# ext_power.net
KiCad netlist of a schematic drawn in Altium Designer
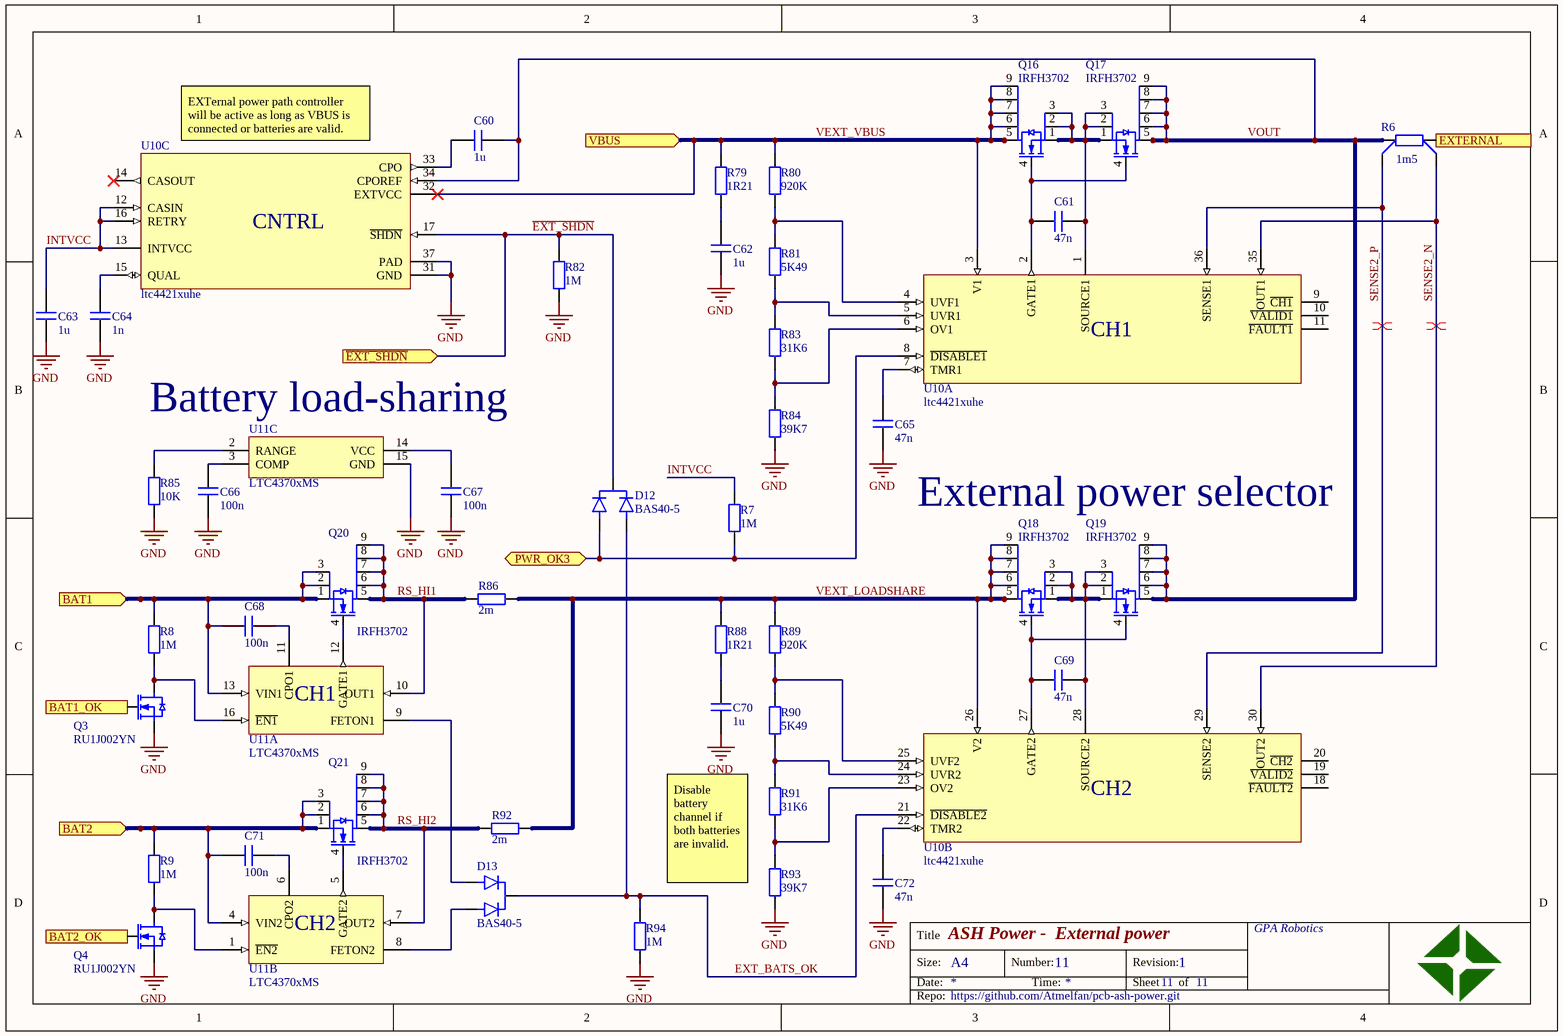
[diagram p0: ext_power.SchDoc]

(export (version "E")
  (design (tool "Eeschema 10.0.6"))
  (components
    (comp (ref "C60")
      (value "1u")
      (footprint "CAPC2012X11N")
      (description "Capacitor")
      (fields (field (name "Comment") "cap"))
      (libsource (lib "lib_passives") (part "cap"))
    )
    (comp (ref "C61")
      (value "47n")
      (footprint "CAPC1005X06N")
      (description "Capacitor")
      (fields (field (name "Comment") "cap"))
      (libsource (lib "lib_passives") (part "cap"))
    )
    (comp (ref "C62")
      (value "1u")
      (footprint "CAPC2012X11N")
      (description "Capacitor")
      (fields (field (name "Comment") "cap"))
      (libsource (lib "lib_passives") (part "cap"))
    )
    (comp (ref "C63")
      (value "1u")
      (footprint "CAPC2012X11N")
      (description "Capacitor")
      (fields (field (name "Comment") "cap"))
      (libsource (lib "lib_passives") (part "cap"))
    )
    (comp (ref "C64")
      (value "1n")
      (footprint "CAPC1005X06N")
      (description "Capacitor")
      (fields (field (name "Comment") "cap"))
      (libsource (lib "lib_passives") (part "cap"))
    )
    (comp (ref "C65")
      (value "47n")
      (footprint "CAPC1005X06N")
      (description "Capacitor")
      (fields (field (name "Comment") "cap"))
      (libsource (lib "lib_passives") (part "cap"))
    )
    (comp (ref "C66")
      (value "100n")
      (footprint "CAPC1005X06N")
      (description "Capacitor")
      (fields (field (name "Comment") "cap"))
      (libsource (lib "lib_passives") (part "cap"))
    )
    (comp (ref "C67")
      (value "100n")
      (footprint "CAPC1005X06N")
      (description "Capacitor")
      (fields (field (name "Comment") "cap"))
      (libsource (lib "lib_passives") (part "cap"))
    )
    (comp (ref "C68")
      (value "100n")
      (footprint "CAPC1005X06N")
      (description "Capacitor")
      (fields (field (name "Comment") "cap"))
      (libsource (lib "lib_passives") (part "cap"))
    )
    (comp (ref "C69")
      (value "47n")
      (footprint "CAPC1005X06N")
      (description "Capacitor")
      (fields (field (name "Comment") "cap"))
      (libsource (lib "lib_passives") (part "cap"))
    )
    (comp (ref "C70")
      (value "1u")
      (footprint "CAPC2012X11N")
      (description "Capacitor")
      (fields (field (name "Comment") "cap"))
      (libsource (lib "lib_passives") (part "cap"))
    )
    (comp (ref "C71")
      (value "100n")
      (footprint "CAPC1005X06N")
      (description "Capacitor")
      (fields (field (name "Comment") "cap"))
      (libsource (lib "lib_passives") (part "cap"))
    )
    (comp (ref "C72")
      (value "47n")
      (footprint "CAPC1005X06N")
      (description "Capacitor")
      (fields (field (name "Comment") "cap"))
      (libsource (lib "lib_passives") (part "cap"))
    )
    (comp (ref "D12")
      (value "BAS40-5")
      (footprint "SOT23_CC")
      (description "Diode Common Cathode")
      (libsource (lib "lib_actives") (part "diode_dual_cc"))
    )
    (comp (ref "D13")
      (value "BAS40-5")
      (footprint "SOT23_CC")
      (description "Diode Common Cathode")
      (libsource (lib "lib_actives") (part "diode_dual_cc"))
    )
    (comp (ref "Q3")
      (value "RU1J002YN")
      (footprint "SOTFL65P210X105-3N")
      (description "N-channel 50V 200mA Small signal MOSFET")
      (libsource (lib "lib_rohm") (part "ru1j002yn"))
    )
    (comp (ref "Q4")
      (value "RU1J002YN")
      (footprint "SOTFL65P210X105-3N")
      (description "N-channel 50V 200mA Small signal MOSFET")
      (libsource (lib "lib_rohm") (part "ru1j002yn"))
    )
    (comp (ref "Q16")
      (value "IRFH3702")
      (footprint "PQFN67P300X300X100-8N")
      (description "HEXFET Power MOSFET")
      (libsource (lib "lib_infineon") (part "irfh3702"))
    )
    (comp (ref "Q17")
      (value "IRFH3702")
      (footprint "PQFN67P300X300X100-8N")
      (description "HEXFET Power MOSFET")
      (libsource (lib "lib_infineon") (part "irfh3702"))
    )
    (comp (ref "Q18")
      (value "IRFH3702")
      (footprint "PQFN67P300X300X100-8N")
      (description "HEXFET Power MOSFET")
      (libsource (lib "lib_infineon") (part "irfh3702"))
    )
    (comp (ref "Q19")
      (value "IRFH3702")
      (footprint "PQFN67P300X300X100-8N")
      (description "HEXFET Power MOSFET")
      (libsource (lib "lib_infineon") (part "irfh3702"))
    )
    (comp (ref "Q20")
      (value "IRFH3702")
      (footprint "PQFN67P300X300X100-8N")
      (description "HEXFET Power MOSFET")
      (libsource (lib "lib_infineon") (part "irfh3702"))
    )
    (comp (ref "Q21")
      (value "IRFH3702")
      (footprint "PQFN67P300X300X100-8N")
      (description "HEXFET Power MOSFET")
      (libsource (lib "lib_infineon") (part "irfh3702"))
    )
    (comp (ref "R6")
      (value "1m5")
      (footprint "4T_RESC1632X05N")
      (description "Resistor")
      (fields (field (name "Comment") "res_4t"))
      (libsource (lib "lib_passives") (part "res_4t"))
    )
    (comp (ref "R7")
      (value "1M")
      (footprint "RESC1005X04N")
      (description "Resistor")
      (fields (field (name "Comment") "res"))
      (libsource (lib "") (part "res_1"))
    )
    (comp (ref "R8")
      (value "1M")
      (footprint "RESC1005X04N")
      (description "Resistor")
      (fields (field (name "Comment") "res"))
      (libsource (lib "lib_passives") (part "res"))
    )
    (comp (ref "R9")
      (value "1M")
      (footprint "RESC1005X04N")
      (description "Resistor")
      (fields (field (name "Comment") "res"))
      (libsource (lib "lib_passives") (part "res"))
    )
    (comp (ref "R79")
      (value "1R21")
      (footprint "RESC2012X06N")
      (description "Resistor")
      (fields (field (name "Comment") "res"))
      (libsource (lib "lib_passives") (part "res"))
    )
    (comp (ref "R80")
      (value "920K")
      (footprint "RESC1005X04N")
      (description "Resistor")
      (fields (field (name "Comment") "res"))
      (libsource (lib "lib_passives") (part "res"))
    )
    (comp (ref "R81")
      (value "5K49")
      (footprint "RESC1005X04N")
      (description "Resistor")
      (fields (field (name "Comment") "res"))
      (libsource (lib "lib_passives") (part "res"))
    )
    (comp (ref "R82")
      (value "1M")
      (footprint "RESC1005X04N")
      (description "Resistor")
      (fields (field (name "Comment") "res"))
      (libsource (lib "") (part "res_1"))
    )
    (comp (ref "R83")
      (value "31K6")
      (footprint "RESC1005X04N")
      (description "Resistor")
      (fields (field (name "Comment") "res"))
      (libsource (lib "lib_passives") (part "res"))
    )
    (comp (ref "R84")
      (value "39K7")
      (footprint "RESC1005X04N")
      (description "Resistor")
      (fields (field (name "Comment") "res"))
      (libsource (lib "lib_passives") (part "res"))
    )
    (comp (ref "R85")
      (value "10K")
      (footprint "RESC1005X04N")
      (description "Resistor")
      (fields (field (name "Comment") "res"))
      (libsource (lib "lib_passives") (part "res"))
    )
    (comp (ref "R86")
      (value "2m")
      (footprint "RESC3216X07N")
      (description "Resistor")
      (fields (field (name "Comment") "res"))
      (libsource (lib "") (part "res_1"))
    )
    (comp (ref "R88")
      (value "1R21")
      (footprint "RESC2012X06N")
      (description "Resistor")
      (fields (field (name "Comment") "res"))
      (libsource (lib "lib_passives") (part "res"))
    )
    (comp (ref "R89")
      (value "920K")
      (footprint "RESC1005X04N")
      (description "Resistor")
      (fields (field (name "Comment") "res"))
      (libsource (lib "lib_passives") (part "res"))
    )
    (comp (ref "R90")
      (value "5K49")
      (footprint "RESC1005X04N")
      (description "Resistor")
      (fields (field (name "Comment") "res"))
      (libsource (lib "lib_passives") (part "res"))
    )
    (comp (ref "R91")
      (value "31K6")
      (footprint "RESC1005X04N")
      (description "Resistor")
      (fields (field (name "Comment") "res"))
      (libsource (lib "lib_passives") (part "res"))
    )
    (comp (ref "R92")
      (value "2m")
      (footprint "RESC3216X07N")
      (description "Resistor")
      (fields (field (name "Comment") "res"))
      (libsource (lib "") (part "res_1"))
    )
    (comp (ref "R93")
      (value "39K7")
      (footprint "RESC1005X04N")
      (description "Resistor")
      (fields (field (name "Comment") "res"))
      (libsource (lib "lib_passives") (part "res"))
    )
    (comp (ref "R94")
      (value "1M")
      (footprint "RESC1005X04N")
      (description "Resistor")
      (fields (field (name "Comment") "res"))
      (libsource (lib "lib_passives") (part "res"))
    )
    (comp (ref "U10")
      (value "ltc4421xuhe")
      (footprint "QFN50P500X600X80_HS-37N_LTC4421")
      (description "High Power Prioritized PowerPath Controller")
      (libsource (lib "lib_analog") (part "ltc4421xuhe"))
    )
    (comp (ref "U11")
      (value "LTC4370xMS")
      (footprint "TSSOP50P510X110-16N_ltc4421")
      (description "Two-Supply Diode-OR Current Balancing Controller")
      (libsource (lib "lib_analog") (part "ltc4370xms"))
    )
  )
  (nets
    (net (code "1") (name "/BAT1") (class "Default")
      (node (ref "C68") (pin "1") (pinfunction "1_1") (pintype "passive"))
      (node (ref "Q20") (pin "1") (pinfunction "S_1") (pintype "passive"))
      (node (ref "Q20") (pin "2") (pinfunction "S_2") (pintype "passive"))
      (node (ref "Q20") (pin "3") (pinfunction "S_3") (pintype "passive"))
      (node (ref "R8") (pin "2") (pinfunction "2_2") (pintype "passive"))
      (node (ref "U11") (pin "13") (pinfunction "VIN1_13") (pintype "input"))
    )
    (net (code "2") (name "/BAT1_OK") (class "Default")
      (node (ref "Q3") (pin "1") (pinfunction "G_1") (pintype "passive"))
    )
    (net (code "3") (name "/BAT2") (class "Default")
      (node (ref "C71") (pin "1") (pinfunction "1_1") (pintype "passive"))
      (node (ref "Q21") (pin "1") (pinfunction "S_1") (pintype "passive"))
      (node (ref "Q21") (pin "2") (pinfunction "S_2") (pintype "passive"))
      (node (ref "Q21") (pin "3") (pinfunction "S_3") (pintype "passive"))
      (node (ref "R9") (pin "2") (pinfunction "2_2") (pintype "passive"))
      (node (ref "U11") (pin "4") (pinfunction "VIN2_4") (pintype "input"))
    )
    (net (code "4") (name "/BAT2_OK") (class "Default")
      (node (ref "Q4") (pin "1") (pinfunction "G_1") (pintype "passive"))
    )
    (net (code "5") (name "/EXTERNAL") (class "Default")
      (node (ref "R6") (pin "2") (pinfunction "2_2") (pintype "passive"))
    )
    (net (code "6") (name "/EXT_BATS_OK") (class "Default")
      (node (ref "D12") (pin "A1") (pinfunction "A1_A1") (pintype "passive"))
      (node (ref "D13") (pin "C") (pinfunction "C_C") (pintype "passive"))
      (node (ref "R94") (pin "2") (pinfunction "2_2") (pintype "passive"))
      (node (ref "U10") (pin "21") (pinfunction "DISABLE2_21") (pintype "input"))
    )
    (net (code "7") (name "/EXT_SHDN") (class "Default")
      (node (ref "D12") (pin "C") (pinfunction "C_C") (pintype "passive"))
      (node (ref "R82") (pin "2") (pinfunction "2_2") (pintype "passive"))
      (node (ref "U10") (pin "17") (pinfunction "SHDN_17") (pintype "input"))
    )
    (net (code "8") (name "/INTVCC") (class "Default")
      (node (ref "C63") (pin "2") (pinfunction "2_2") (pintype "passive"))
      (node (ref "R7") (pin "2") (pinfunction "2_2") (pintype "passive"))
      (node (ref "U10") (pin "12") (pinfunction "CASIN_12") (pintype "input"))
      (node (ref "U10") (pin "13") (pinfunction "INTVCC_13") (pintype "power_in"))
      (node (ref "U10") (pin "16") (pinfunction "RETRY_16") (pintype "input"))
    )
    (net (code "9") (name "/PWR_OK3") (class "Default")
      (node (ref "D12") (pin "A2") (pinfunction "A2_A2") (pintype "passive"))
      (node (ref "R7") (pin "1") (pinfunction "1_1") (pintype "passive"))
      (node (ref "U10") (pin "8") (pinfunction "DISABLE1_8") (pintype "input"))
    )
    (net (code "10") (name "/RS_HI1") (class "Default")
      (node (ref "Q20") (pin "5") (pinfunction "D_5") (pintype "passive"))
      (node (ref "Q20") (pin "6") (pinfunction "D_6") (pintype "passive"))
      (node (ref "Q20") (pin "7") (pinfunction "D_7") (pintype "passive"))
      (node (ref "Q20") (pin "8") (pinfunction "D_8") (pintype "passive"))
      (node (ref "Q20") (pin "9") (pinfunction "D_9") (pintype "passive"))
      (node (ref "R86") (pin "1") (pinfunction "1_1") (pintype "passive"))
      (node (ref "U11") (pin "10") (pinfunction "OUT1_10") (pintype "input"))
    )
    (net (code "11") (name "/RS_HI2") (class "Default")
      (node (ref "Q21") (pin "5") (pinfunction "D_5") (pintype "passive"))
      (node (ref "Q21") (pin "6") (pinfunction "D_6") (pintype "passive"))
      (node (ref "Q21") (pin "7") (pinfunction "D_7") (pintype "passive"))
      (node (ref "Q21") (pin "8") (pinfunction "D_8") (pintype "passive"))
      (node (ref "Q21") (pin "9") (pinfunction "D_9") (pintype "passive"))
      (node (ref "R92") (pin "1") (pinfunction "1_1") (pintype "passive"))
      (node (ref "U11") (pin "7") (pinfunction "OUT2_7") (pintype "input"))
    )
    (net (code "12") (name "/SENSE2_N") (class "Default")
      (node (ref "R6") (pin "4") (pinfunction "4_4") (pintype "passive"))
      (node (ref "U10") (pin "30") (pinfunction "OUT2_30") (pintype "input"))
      (node (ref "U10") (pin "35") (pinfunction "OUT1_35") (pintype "input"))
    )
    (net (code "13") (name "/SENSE2_P") (class "Default")
      (node (ref "R6") (pin "3") (pinfunction "3_3") (pintype "passive"))
      (node (ref "U10") (pin "29") (pinfunction "SENSE2_29") (pintype "input"))
      (node (ref "U10") (pin "36") (pinfunction "SENSE1_36") (pintype "input"))
    )
    (net (code "14") (name "/VEXT_LOADSHARE") (class "Default")
      (node (ref "Q18") (pin "5") (pinfunction "D_5") (pintype "passive"))
      (node (ref "Q18") (pin "6") (pinfunction "D_6") (pintype "passive"))
      (node (ref "Q18") (pin "7") (pinfunction "D_7") (pintype "passive"))
      (node (ref "Q18") (pin "8") (pinfunction "D_8") (pintype "passive"))
      (node (ref "Q18") (pin "9") (pinfunction "D_9") (pintype "passive"))
      (node (ref "R86") (pin "2") (pinfunction "2_2") (pintype "passive"))
      (node (ref "R88") (pin "2") (pinfunction "2_2") (pintype "passive"))
      (node (ref "R89") (pin "2") (pinfunction "2_2") (pintype "passive"))
      (node (ref "R92") (pin "2") (pinfunction "2_2") (pintype "passive"))
      (node (ref "U10") (pin "26") (pinfunction "V2_26") (pintype "input"))
    )
    (net (code "15") (name "/VEXT_VBUS") (class "Default")
      (node (ref "Q16") (pin "5") (pinfunction "D_5") (pintype "passive"))
      (node (ref "Q16") (pin "6") (pinfunction "D_6") (pintype "passive"))
      (node (ref "Q16") (pin "7") (pinfunction "D_7") (pintype "passive"))
      (node (ref "Q16") (pin "8") (pinfunction "D_8") (pintype "passive"))
      (node (ref "Q16") (pin "9") (pinfunction "D_9") (pintype "passive"))
      (node (ref "R79") (pin "2") (pinfunction "2_2") (pintype "passive"))
      (node (ref "R80") (pin "2") (pinfunction "2_2") (pintype "passive"))
      (node (ref "U10") (pin "3") (pinfunction "V1_3") (pintype "input"))
      (node (ref "U10") (pin "32") (pinfunction "EXTVCC_32") (pintype "power_in"))
    )
    (net (code "16") (name "/VOUT") (class "Default")
      (node (ref "C60") (pin "2") (pinfunction "2_2") (pintype "passive"))
      (node (ref "Q17") (pin "5") (pinfunction "D_5") (pintype "passive"))
      (node (ref "Q17") (pin "6") (pinfunction "D_6") (pintype "passive"))
      (node (ref "Q17") (pin "7") (pinfunction "D_7") (pintype "passive"))
      (node (ref "Q17") (pin "8") (pinfunction "D_8") (pintype "passive"))
      (node (ref "Q17") (pin "9") (pinfunction "D_9") (pintype "passive"))
      (node (ref "Q19") (pin "5") (pinfunction "D_5") (pintype "passive"))
      (node (ref "Q19") (pin "6") (pinfunction "D_6") (pintype "passive"))
      (node (ref "Q19") (pin "7") (pinfunction "D_7") (pintype "passive"))
      (node (ref "Q19") (pin "8") (pinfunction "D_8") (pintype "passive"))
      (node (ref "Q19") (pin "9") (pinfunction "D_9") (pintype "passive"))
      (node (ref "R6") (pin "1") (pinfunction "1_1") (pintype "passive"))
      (node (ref "U10") (pin "34") (pinfunction "CPOREF_34") (pintype "input"))
    )
    (net (code "17") (name "GND") (class "Default")
      (node (ref "C62") (pin "1") (pinfunction "1_1") (pintype "passive"))
      (node (ref "C63") (pin "1") (pinfunction "1_1") (pintype "passive"))
      (node (ref "C64") (pin "1") (pinfunction "1_1") (pintype "passive"))
      (node (ref "C65") (pin "1") (pinfunction "1_1") (pintype "passive"))
      (node (ref "C66") (pin "1") (pinfunction "1_1") (pintype "passive"))
      (node (ref "C67") (pin "1") (pinfunction "1_1") (pintype "passive"))
      (node (ref "C70") (pin "1") (pinfunction "1_1") (pintype "passive"))
      (node (ref "C72") (pin "1") (pinfunction "1_1") (pintype "passive"))
      (node (ref "Q3") (pin "2") (pinfunction "S_2") (pintype "passive"))
      (node (ref "Q4") (pin "2") (pinfunction "S_2") (pintype "passive"))
      (node (ref "R82") (pin "1") (pinfunction "1_1") (pintype "passive"))
      (node (ref "R84") (pin "1") (pinfunction "1_1") (pintype "passive"))
      (node (ref "R85") (pin "1") (pinfunction "1_1") (pintype "passive"))
      (node (ref "R93") (pin "1") (pinfunction "1_1") (pintype "passive"))
      (node (ref "R94") (pin "1") (pinfunction "1_1") (pintype "passive"))
      (node (ref "U10") (pin "31") (pinfunction "GND_31") (pintype "power_in"))
      (node (ref "U10") (pin "37") (pinfunction "PAD_37") (pintype "power_in"))
      (node (ref "U11") (pin "15") (pinfunction "GND_15") (pintype "power_in"))
    )
    (net (code "18") (name "Net-(C62-Pad2)") (class "Default")
      (node (ref "C62") (pin "2") (pinfunction "2_2") (pintype "passive"))
      (node (ref "R79") (pin "1") (pinfunction "1_1") (pintype "passive"))
    )
    (net (code "19") (name "Net-(C70-Pad2)") (class "Default")
      (node (ref "C70") (pin "2") (pinfunction "2_2") (pintype "passive"))
      (node (ref "R88") (pin "1") (pinfunction "1_1") (pintype "passive"))
    )
    (net (code "20") (name "Net-(Q3-D)") (class "Default")
      (node (ref "Q3") (pin "3") (pinfunction "D_3") (pintype "passive"))
      (node (ref "R8") (pin "1") (pinfunction "1_1") (pintype "passive"))
      (node (ref "U11") (pin "16") (pinfunction "EN1_16") (pintype "input"))
    )
    (net (code "21") (name "Net-(Q4-D)") (class "Default")
      (node (ref "Q4") (pin "3") (pinfunction "D_3") (pintype "passive"))
      (node (ref "R9") (pin "1") (pinfunction "1_1") (pintype "passive"))
      (node (ref "U11") (pin "1") (pinfunction "EN2_1") (pintype "input"))
    )
    (net (code "22") (name "Net-(Q16-G)") (class "Default")
      (node (ref "C61") (pin "1") (pinfunction "1_1") (pintype "passive"))
      (node (ref "Q16") (pin "4") (pinfunction "G_4") (pintype "passive"))
      (node (ref "Q17") (pin "4") (pinfunction "G_4") (pintype "passive"))
      (node (ref "U10") (pin "2") (pinfunction "GATE1_2") (pintype "output"))
    )
    (net (code "23") (name "Net-(Q18-G)") (class "Default")
      (node (ref "C69") (pin "1") (pinfunction "1_1") (pintype "passive"))
      (node (ref "Q18") (pin "4") (pinfunction "G_4") (pintype "passive"))
      (node (ref "Q19") (pin "4") (pinfunction "G_4") (pintype "passive"))
      (node (ref "U10") (pin "27") (pinfunction "GATE2_27") (pintype "output"))
    )
    (net (code "24") (name "Net-(Q20-G)") (class "Default")
      (node (ref "Q20") (pin "4") (pinfunction "G_4") (pintype "passive"))
      (node (ref "U11") (pin "12") (pinfunction "GATE1_12") (pintype "output"))
    )
    (net (code "25") (name "Net-(Q21-G)") (class "Default")
      (node (ref "Q21") (pin "4") (pinfunction "G_4") (pintype "passive"))
      (node (ref "U11") (pin "5") (pinfunction "GATE2_5") (pintype "output"))
    )
    (net (code "26") (name "Net-(U10A-OV1)") (class "Default")
      (node (ref "R83") (pin "1") (pinfunction "1_1") (pintype "passive"))
      (node (ref "R84") (pin "2") (pinfunction "2_2") (pintype "passive"))
      (node (ref "U10") (pin "6") (pinfunction "OV1_6") (pintype "input"))
    )
    (net (code "27") (name "Net-(U10A-SOURCE1)") (class "Default")
      (node (ref "C61") (pin "2") (pinfunction "2_2") (pintype "passive"))
      (node (ref "Q16") (pin "1") (pinfunction "S_1") (pintype "passive"))
      (node (ref "Q16") (pin "2") (pinfunction "S_2") (pintype "passive"))
      (node (ref "Q16") (pin "3") (pinfunction "S_3") (pintype "passive"))
      (node (ref "Q17") (pin "1") (pinfunction "S_1") (pintype "passive"))
      (node (ref "Q17") (pin "2") (pinfunction "S_2") (pintype "passive"))
      (node (ref "Q17") (pin "3") (pinfunction "S_3") (pintype "passive"))
      (node (ref "U10") (pin "1") (pinfunction "SOURCE1_1") (pintype "passive"))
    )
    (net (code "28") (name "Net-(U10A-TMR1)") (class "Default")
      (node (ref "C65") (pin "2") (pinfunction "2_2") (pintype "passive"))
      (node (ref "U10") (pin "7") (pinfunction "TMR1_7") (pintype "bidirectional"))
    )
    (net (code "29") (name "Net-(U10A-UVF1)") (class "Default")
      (node (ref "R80") (pin "1") (pinfunction "1_1") (pintype "passive"))
      (node (ref "R81") (pin "2") (pinfunction "2_2") (pintype "passive"))
      (node (ref "U10") (pin "4") (pinfunction "UVF1_4") (pintype "input"))
    )
    (net (code "30") (name "Net-(U10A-UVR1)") (class "Default")
      (node (ref "R81") (pin "1") (pinfunction "1_1") (pintype "passive"))
      (node (ref "R83") (pin "2") (pinfunction "2_2") (pintype "passive"))
      (node (ref "U10") (pin "5") (pinfunction "UVR1_5") (pintype "input"))
    )
    (net (code "31") (name "Net-(U10B-OV2)") (class "Default")
      (node (ref "R91") (pin "1") (pinfunction "1_1") (pintype "passive"))
      (node (ref "R93") (pin "2") (pinfunction "2_2") (pintype "passive"))
      (node (ref "U10") (pin "23") (pinfunction "OV2_23") (pintype "input"))
    )
    (net (code "32") (name "Net-(U10B-SOURCE2)") (class "Default")
      (node (ref "C69") (pin "2") (pinfunction "2_2") (pintype "passive"))
      (node (ref "Q18") (pin "1") (pinfunction "S_1") (pintype "passive"))
      (node (ref "Q18") (pin "2") (pinfunction "S_2") (pintype "passive"))
      (node (ref "Q18") (pin "3") (pinfunction "S_3") (pintype "passive"))
      (node (ref "Q19") (pin "1") (pinfunction "S_1") (pintype "passive"))
      (node (ref "Q19") (pin "2") (pinfunction "S_2") (pintype "passive"))
      (node (ref "Q19") (pin "3") (pinfunction "S_3") (pintype "passive"))
      (node (ref "U10") (pin "28") (pinfunction "SOURCE2_28") (pintype "passive"))
    )
    (net (code "33") (name "Net-(U10B-TMR2)") (class "Default")
      (node (ref "C72") (pin "2") (pinfunction "2_2") (pintype "passive"))
      (node (ref "U10") (pin "22") (pinfunction "TMR2_22") (pintype "bidirectional"))
    )
    (net (code "34") (name "Net-(U10B-UVF2)") (class "Default")
      (node (ref "R89") (pin "1") (pinfunction "1_1") (pintype "passive"))
      (node (ref "R90") (pin "2") (pinfunction "2_2") (pintype "passive"))
      (node (ref "U10") (pin "25") (pinfunction "UVF2_25") (pintype "input"))
    )
    (net (code "35") (name "Net-(U10B-UVR2)") (class "Default")
      (node (ref "R90") (pin "1") (pinfunction "1_1") (pintype "passive"))
      (node (ref "R91") (pin "2") (pinfunction "2_2") (pintype "passive"))
      (node (ref "U10") (pin "24") (pinfunction "UVR2_24") (pintype "input"))
    )
    (net (code "36") (name "Net-(U10C-CPO)") (class "Default")
      (node (ref "C60") (pin "1") (pinfunction "1_1") (pintype "passive"))
      (node (ref "U10") (pin "33") (pinfunction "CPO_33") (pintype "output"))
    )
    (net (code "37") (name "Net-(U10C-QUAL)") (class "Default")
      (node (ref "C64") (pin "2") (pinfunction "2_2") (pintype "passive"))
      (node (ref "U10") (pin "15") (pinfunction "QUAL_15") (pintype "bidirectional"))
    )
    (net (code "38") (name "Net-(U11A-CPO1)") (class "Default")
      (node (ref "C68") (pin "2") (pinfunction "2_2") (pintype "passive"))
      (node (ref "U11") (pin "11") (pinfunction "CPO1_11") (pintype "passive"))
    )
    (net (code "39") (name "Net-(U11A-FETON1)") (class "Default")
      (node (ref "D13") (pin "A1") (pinfunction "A1_A1") (pintype "passive"))
      (node (ref "U11") (pin "9") (pinfunction "FETON1_9") (pintype "open_collector"))
    )
    (net (code "40") (name "Net-(U11B-CPO2)") (class "Default")
      (node (ref "C71") (pin "2") (pinfunction "2_2") (pintype "passive"))
      (node (ref "U11") (pin "6") (pinfunction "CPO2_6") (pintype "passive"))
    )
    (net (code "41") (name "Net-(U11B-FETON2)") (class "Default")
      (node (ref "D13") (pin "A2") (pinfunction "A2_A2") (pintype "passive"))
      (node (ref "U11") (pin "8") (pinfunction "FETON2_8") (pintype "open_collector"))
    )
    (net (code "42") (name "Net-(U11C-COMP)") (class "Default")
      (node (ref "C66") (pin "2") (pinfunction "2_2") (pintype "passive"))
      (node (ref "U11") (pin "3") (pinfunction "COMP_3") (pintype "passive"))
    )
    (net (code "43") (name "Net-(U11C-RANGE)") (class "Default")
      (node (ref "R85") (pin "2") (pinfunction "2_2") (pintype "passive"))
      (node (ref "U11") (pin "2") (pinfunction "RANGE_2") (pintype "passive"))
    )
    (net (code "44") (name "Net-(U11C-VCC)") (class "Default")
      (node (ref "C67") (pin "2") (pinfunction "2_2") (pintype "passive"))
      (node (ref "U11") (pin "14") (pinfunction "VCC_14") (pintype "power_in"))
    )
    (net (code "45") (name "unconnected-(U10A-CH1-Pad9)") (class "Default")
      (node (ref "U10") (pin "9") (pinfunction "CH1_9") (pintype "open_collector"))
    )
    (net (code "46") (name "unconnected-(U10A-FAULT1-Pad11)") (class "Default")
      (node (ref "U10") (pin "11") (pinfunction "FAULT1_11") (pintype "open_collector"))
    )
    (net (code "47") (name "unconnected-(U10A-VALID1-Pad10)") (class "Default")
      (node (ref "U10") (pin "10") (pinfunction "VALID1_10") (pintype "open_collector"))
    )
    (net (code "48") (name "unconnected-(U10B-CH2-Pad20)") (class "Default")
      (node (ref "U10") (pin "20") (pinfunction "CH2_20") (pintype "open_collector"))
    )
    (net (code "49") (name "unconnected-(U10B-FAULT2-Pad18)") (class "Default")
      (node (ref "U10") (pin "18") (pinfunction "FAULT2_18") (pintype "open_collector"))
    )
    (net (code "50") (name "unconnected-(U10B-VALID2-Pad19)") (class "Default")
      (node (ref "U10") (pin "19") (pinfunction "VALID2_19") (pintype "open_collector"))
    )
    (net (code "51") (name "unconnected-(U10C-CASOUT-Pad14)") (class "Default")
      (node (ref "U10") (pin "14") (pinfunction "CASOUT_14") (pintype "output+no_connect"))
    )
  )
)
